# BareBonesArduino.net
KiCad netlist of a schematic drawn in EAGLE
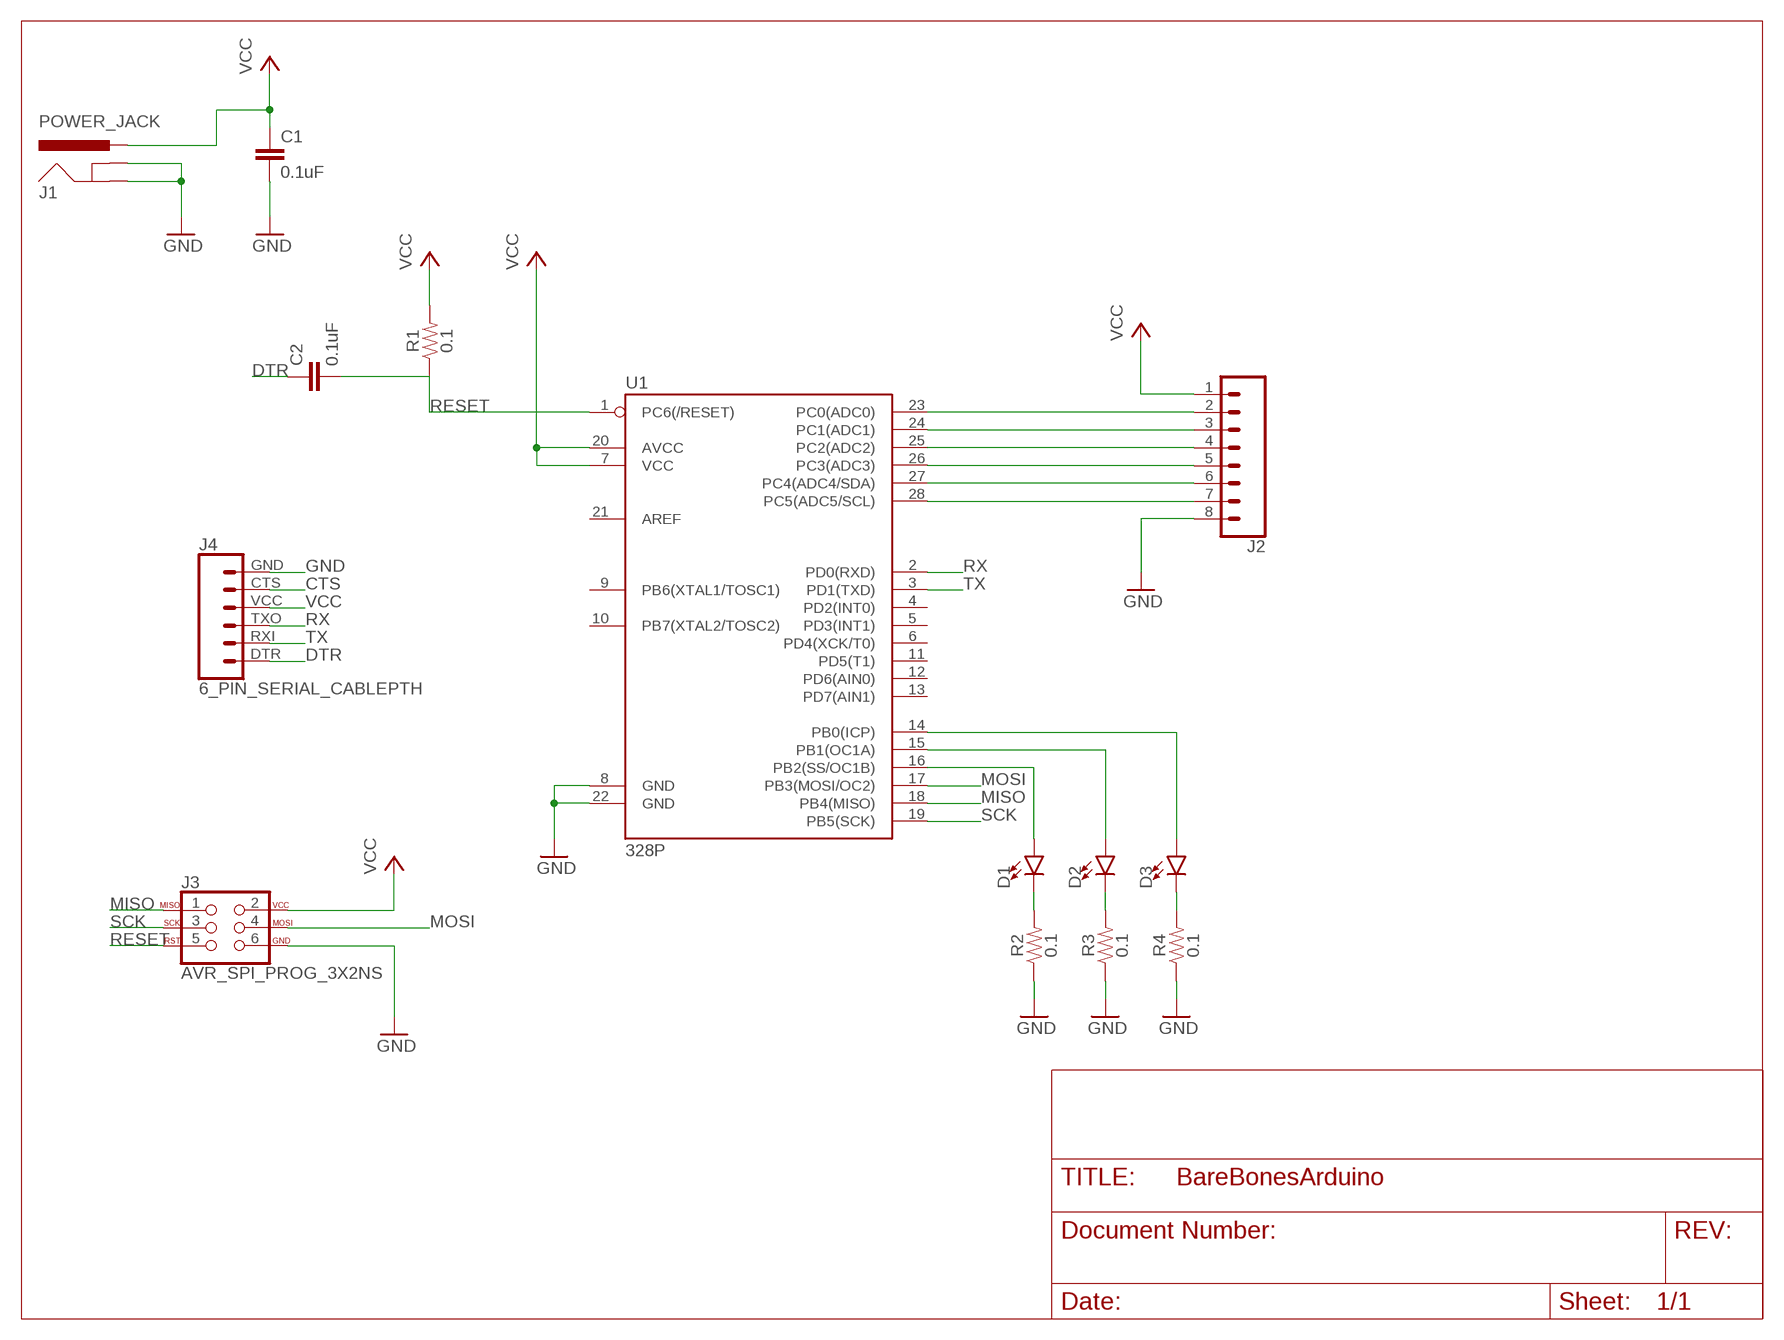
[diagram p0: schematic, sheet 1]

(export (version "E")
  (design (tool "Eeschema 10.0.6"))
  (components
    (comp (ref "C1")
      (value "0.1uF")
      (footprint "eagle-import:0402")
      (libsource (lib "eagle-import") (part "0.1UF-0402-16V-10%"))
    )
    (comp (ref "C2")
      (value "0.1uF")
      (footprint "eagle-import:0402")
      (libsource (lib "eagle-import") (part "0.1UF-0402-16V-10%"))
    )
    (comp (ref "D1")
      (value "LED5MM")
      (footprint "eagle-import:LED_5MM")
      (libsource (lib "eagle-import") (part "LED5MM"))
    )
    (comp (ref "D2")
      (value "LED5MM")
      (footprint "eagle-import:LED_5MM")
      (libsource (lib "eagle-import") (part "LED5MM"))
    )
    (comp (ref "D3")
      (value "LED5MM")
      (footprint "eagle-import:LED_5MM")
      (libsource (lib "eagle-import") (part "LED5MM"))
    )
    (comp (ref "J1")
      (value "POWER_JACK")
      (footprint "eagle-import:POWER_JACK_PTH")
      (libsource (lib "eagle-import") (part "POWER_JACK"))
    )
    (comp (ref "J2")
      (value "CONN_08\"")
      (footprint "eagle-import:1X08")
      (libsource (lib "eagle-import") (part "CONN_08{dblquote}"))
    )
    (comp (ref "J3")
      (value "AVR_SPI_PROG_3X2NS")
      (footprint "eagle-import:2X3-NS")
      (libsource (lib "eagle-import") (part "AVR_SPI_PROG_3X2NS"))
    )
    (comp (ref "J4")
      (value "6_PIN_SERIAL_CABLEPTH")
      (footprint "eagle-import:FTDI_BASIC")
      (libsource (lib "eagle-import") (part "6_PIN_SERIAL_CABLEPTH"))
    )
    (comp (ref "R1")
      (value "0.1")
      (footprint "eagle-import:1210")
      (libsource (lib "eagle-import") (part "0.1OHM-1210-1/2W-1%"))
    )
    (comp (ref "R2")
      (value "0.1")
      (footprint "eagle-import:1210")
      (libsource (lib "eagle-import") (part "0.1OHM-1210-1/2W-1%"))
    )
    (comp (ref "R3")
      (value "0.1")
      (footprint "eagle-import:1210")
      (libsource (lib "eagle-import") (part "0.1OHM-1210-1/2W-1%"))
    )
    (comp (ref "R4")
      (value "0.1")
      (footprint "eagle-import:1210")
      (libsource (lib "eagle-import") (part "0.1OHM-1210-1/2W-1%"))
    )
    (comp (ref "U1")
      (value "328P")
      (footprint "eagle-import:DIP28")
      (libsource (lib "eagle-import") (part "ATMEGA328P_PDIP"))
    )
  )
  (nets
    (net (code "1") (name "/CTS") (class "Default")
      (node (ref "J4") (pin "CTS") (pinfunction "5_CTS") (pintype "passive"))
    )
    (net (code "2") (name "/DTR") (class "Default")
      (node (ref "C2") (pin "1") (pinfunction "1_1") (pintype "passive"))
      (node (ref "J4") (pin "DTR") (pinfunction "1_DTR") (pintype "passive"))
    )
    (net (code "3") (name "/MISO") (class "Default")
      (node (ref "J3") (pin "1") (pinfunction "1_1") (pintype "passive"))
      (node (ref "U1") (pin "18") (pinfunction "PB4(MISO)_18") (pintype "bidirectional"))
    )
    (net (code "4") (name "/MOSI") (class "Default")
      (node (ref "J3") (pin "4") (pinfunction "4_4") (pintype "passive"))
      (node (ref "U1") (pin "17") (pinfunction "PB3(MOSI/OC2)_17") (pintype "bidirectional"))
    )
    (net (code "5") (name "/RESET") (class "Default")
      (node (ref "C2") (pin "2") (pinfunction "2_2") (pintype "passive"))
      (node (ref "J3") (pin "5") (pinfunction "5_5") (pintype "passive"))
      (node (ref "R1") (pin "1") (pinfunction "1_1") (pintype "passive"))
      (node (ref "U1") (pin "1") (pinfunction "PC6(/RESET)_1") (pintype "bidirectional"))
    )
    (net (code "6") (name "/RX") (class "Default")
      (node (ref "J4") (pin "TXO") (pinfunction "3_TXO") (pintype "passive"))
      (node (ref "U1") (pin "2") (pinfunction "PD0(RXD)_2") (pintype "bidirectional"))
    )
    (net (code "7") (name "/SCK") (class "Default")
      (node (ref "J3") (pin "3") (pinfunction "3_3") (pintype "passive"))
      (node (ref "U1") (pin "19") (pinfunction "PB5(SCK)_19") (pintype "bidirectional"))
    )
    (net (code "8") (name "/TX") (class "Default")
      (node (ref "J4") (pin "RXI") (pinfunction "2_RXI") (pintype "passive"))
      (node (ref "U1") (pin "3") (pinfunction "PD1(TXD)_3") (pintype "bidirectional"))
    )
    (net (code "9") (name "GND") (class "Default")
      (node (ref "C1") (pin "2") (pinfunction "2_2") (pintype "passive"))
      (node (ref "J1") (pin "GND") (pinfunction "GND_GND") (pintype "bidirectional"))
      (node (ref "J1") (pin "GNDBREAK") (pinfunction "GNDBREAK_GNDBREAK") (pintype "bidirectional"))
      (node (ref "J2") (pin "8") (pinfunction "8_8") (pintype "passive"))
      (node (ref "J3") (pin "6") (pinfunction "6_6") (pintype "passive"))
      (node (ref "J4") (pin "GND") (pinfunction "6_GND") (pintype "passive"))
      (node (ref "R2") (pin "1") (pinfunction "1_1") (pintype "passive"))
      (node (ref "R3") (pin "1") (pinfunction "1_1") (pintype "passive"))
      (node (ref "R4") (pin "1") (pinfunction "1_1") (pintype "passive"))
      (node (ref "U1") (pin "22") (pinfunction "GND_22") (pintype "bidirectional"))
      (node (ref "U1") (pin "8") (pinfunction "GND_8") (pintype "bidirectional"))
    )
    (net (code "10") (name "Net-(D1-C)") (class "Default")
      (node (ref "D1") (pin "K") (pinfunction "C_K") (pintype "passive"))
      (node (ref "R2") (pin "2") (pinfunction "2_2") (pintype "passive"))
    )
    (net (code "11") (name "Net-(D2-C)") (class "Default")
      (node (ref "D2") (pin "K") (pinfunction "C_K") (pintype "passive"))
      (node (ref "R3") (pin "2") (pinfunction "2_2") (pintype "passive"))
    )
    (net (code "12") (name "Net-(D3-C)") (class "Default")
      (node (ref "D3") (pin "K") (pinfunction "C_K") (pintype "passive"))
      (node (ref "R4") (pin "2") (pinfunction "2_2") (pintype "passive"))
    )
    (net (code "13") (name "Net-(U1-PB0(ICP))") (class "Default")
      (node (ref "D3") (pin "A") (pinfunction "A_A") (pintype "passive"))
      (node (ref "U1") (pin "14") (pinfunction "PB0(ICP)_14") (pintype "bidirectional"))
    )
    (net (code "14") (name "Net-(U1-PB1(OC1A))") (class "Default")
      (node (ref "D2") (pin "A") (pinfunction "A_A") (pintype "passive"))
      (node (ref "U1") (pin "15") (pinfunction "PB1(OC1A)_15") (pintype "bidirectional"))
    )
    (net (code "15") (name "Net-(U1-PB2(SS{slash}OC1B))") (class "Default")
      (node (ref "D1") (pin "A") (pinfunction "A_A") (pintype "passive"))
      (node (ref "U1") (pin "16") (pinfunction "PB2(SS/OC1B)_16") (pintype "bidirectional"))
    )
    (net (code "16") (name "Net-(U1-PC0(ADC0))") (class "Default")
      (node (ref "J2") (pin "2") (pinfunction "2_2") (pintype "passive"))
      (node (ref "U1") (pin "23") (pinfunction "PC0(ADC0)_23") (pintype "bidirectional"))
    )
    (net (code "17") (name "Net-(U1-PC1(ADC1))") (class "Default")
      (node (ref "J2") (pin "3") (pinfunction "3_3") (pintype "passive"))
      (node (ref "U1") (pin "24") (pinfunction "PC1(ADC1)_24") (pintype "bidirectional"))
    )
    (net (code "18") (name "Net-(U1-PC2(ADC2))") (class "Default")
      (node (ref "J2") (pin "4") (pinfunction "4_4") (pintype "passive"))
      (node (ref "U1") (pin "25") (pinfunction "PC2(ADC2)_25") (pintype "bidirectional"))
    )
    (net (code "19") (name "Net-(U1-PC3(ADC3))") (class "Default")
      (node (ref "J2") (pin "5") (pinfunction "5_5") (pintype "passive"))
      (node (ref "U1") (pin "26") (pinfunction "PC3(ADC3)_26") (pintype "bidirectional"))
    )
    (net (code "20") (name "Net-(U1-PC4(ADC4{slash}SDA))") (class "Default")
      (node (ref "J2") (pin "6") (pinfunction "6_6") (pintype "passive"))
      (node (ref "U1") (pin "27") (pinfunction "PC4(ADC4/SDA)_27") (pintype "bidirectional"))
    )
    (net (code "21") (name "Net-(U1-PC5(ADC5{slash}SCL))") (class "Default")
      (node (ref "J2") (pin "7") (pinfunction "7_7") (pintype "passive"))
      (node (ref "U1") (pin "28") (pinfunction "PC5(ADC5/SCL)_28") (pintype "bidirectional"))
    )
    (net (code "22") (name "VCC") (class "Default")
      (node (ref "C1") (pin "1") (pinfunction "1_1") (pintype "passive"))
      (node (ref "J1") (pin "PWR") (pinfunction "PWR_PWR") (pintype "bidirectional"))
      (node (ref "J2") (pin "1") (pinfunction "1_1") (pintype "passive"))
      (node (ref "J3") (pin "2") (pinfunction "2_2") (pintype "passive"))
      (node (ref "J4") (pin "VCC") (pinfunction "4_VCC") (pintype "passive"))
      (node (ref "R1") (pin "2") (pinfunction "2_2") (pintype "passive"))
      (node (ref "U1") (pin "20") (pinfunction "AVCC_20") (pintype "bidirectional"))
      (node (ref "U1") (pin "7") (pinfunction "VCC_7") (pintype "bidirectional"))
    )
    (net (code "23") (name "unconnected-(U1-AREF-Pad21)") (class "Default")
      (node (ref "U1") (pin "21") (pinfunction "AREF_21") (pintype "bidirectional"))
    )
    (net (code "24") (name "unconnected-(U1-PB6(XTAL1{slash}TOSC1)-Pad9)") (class "Default")
      (node (ref "U1") (pin "9") (pinfunction "PB6(XTAL1/TOSC1)_9") (pintype "bidirectional"))
    )
    (net (code "25") (name "unconnected-(U1-PB7(XTAL2{slash}TOSC2)-Pad10)") (class "Default")
      (node (ref "U1") (pin "10") (pinfunction "PB7(XTAL2/TOSC2)_10") (pintype "bidirectional"))
    )
    (net (code "26") (name "unconnected-(U1-PD2(INT0)-Pad4)") (class "Default")
      (node (ref "U1") (pin "4") (pinfunction "PD2(INT0)_4") (pintype "bidirectional"))
    )
    (net (code "27") (name "unconnected-(U1-PD3(INT1)-Pad5)") (class "Default")
      (node (ref "U1") (pin "5") (pinfunction "PD3(INT1)_5") (pintype "bidirectional"))
    )
    (net (code "28") (name "unconnected-(U1-PD4(XCK{slash}T0)-Pad6)") (class "Default")
      (node (ref "U1") (pin "6") (pinfunction "PD4(XCK/T0)_6") (pintype "bidirectional"))
    )
    (net (code "29") (name "unconnected-(U1-PD5(T1)-Pad11)") (class "Default")
      (node (ref "U1") (pin "11") (pinfunction "PD5(T1)_11") (pintype "bidirectional"))
    )
    (net (code "30") (name "unconnected-(U1-PD6(AIN0)-Pad12)") (class "Default")
      (node (ref "U1") (pin "12") (pinfunction "PD6(AIN0)_12") (pintype "bidirectional"))
    )
    (net (code "31") (name "unconnected-(U1-PD7(AIN1)-Pad13)") (class "Default")
      (node (ref "U1") (pin "13") (pinfunction "PD7(AIN1)_13") (pintype "bidirectional"))
    )
  )
)
